# Processor.net
KiCad netlist of a schematic drawn in Altium Designer
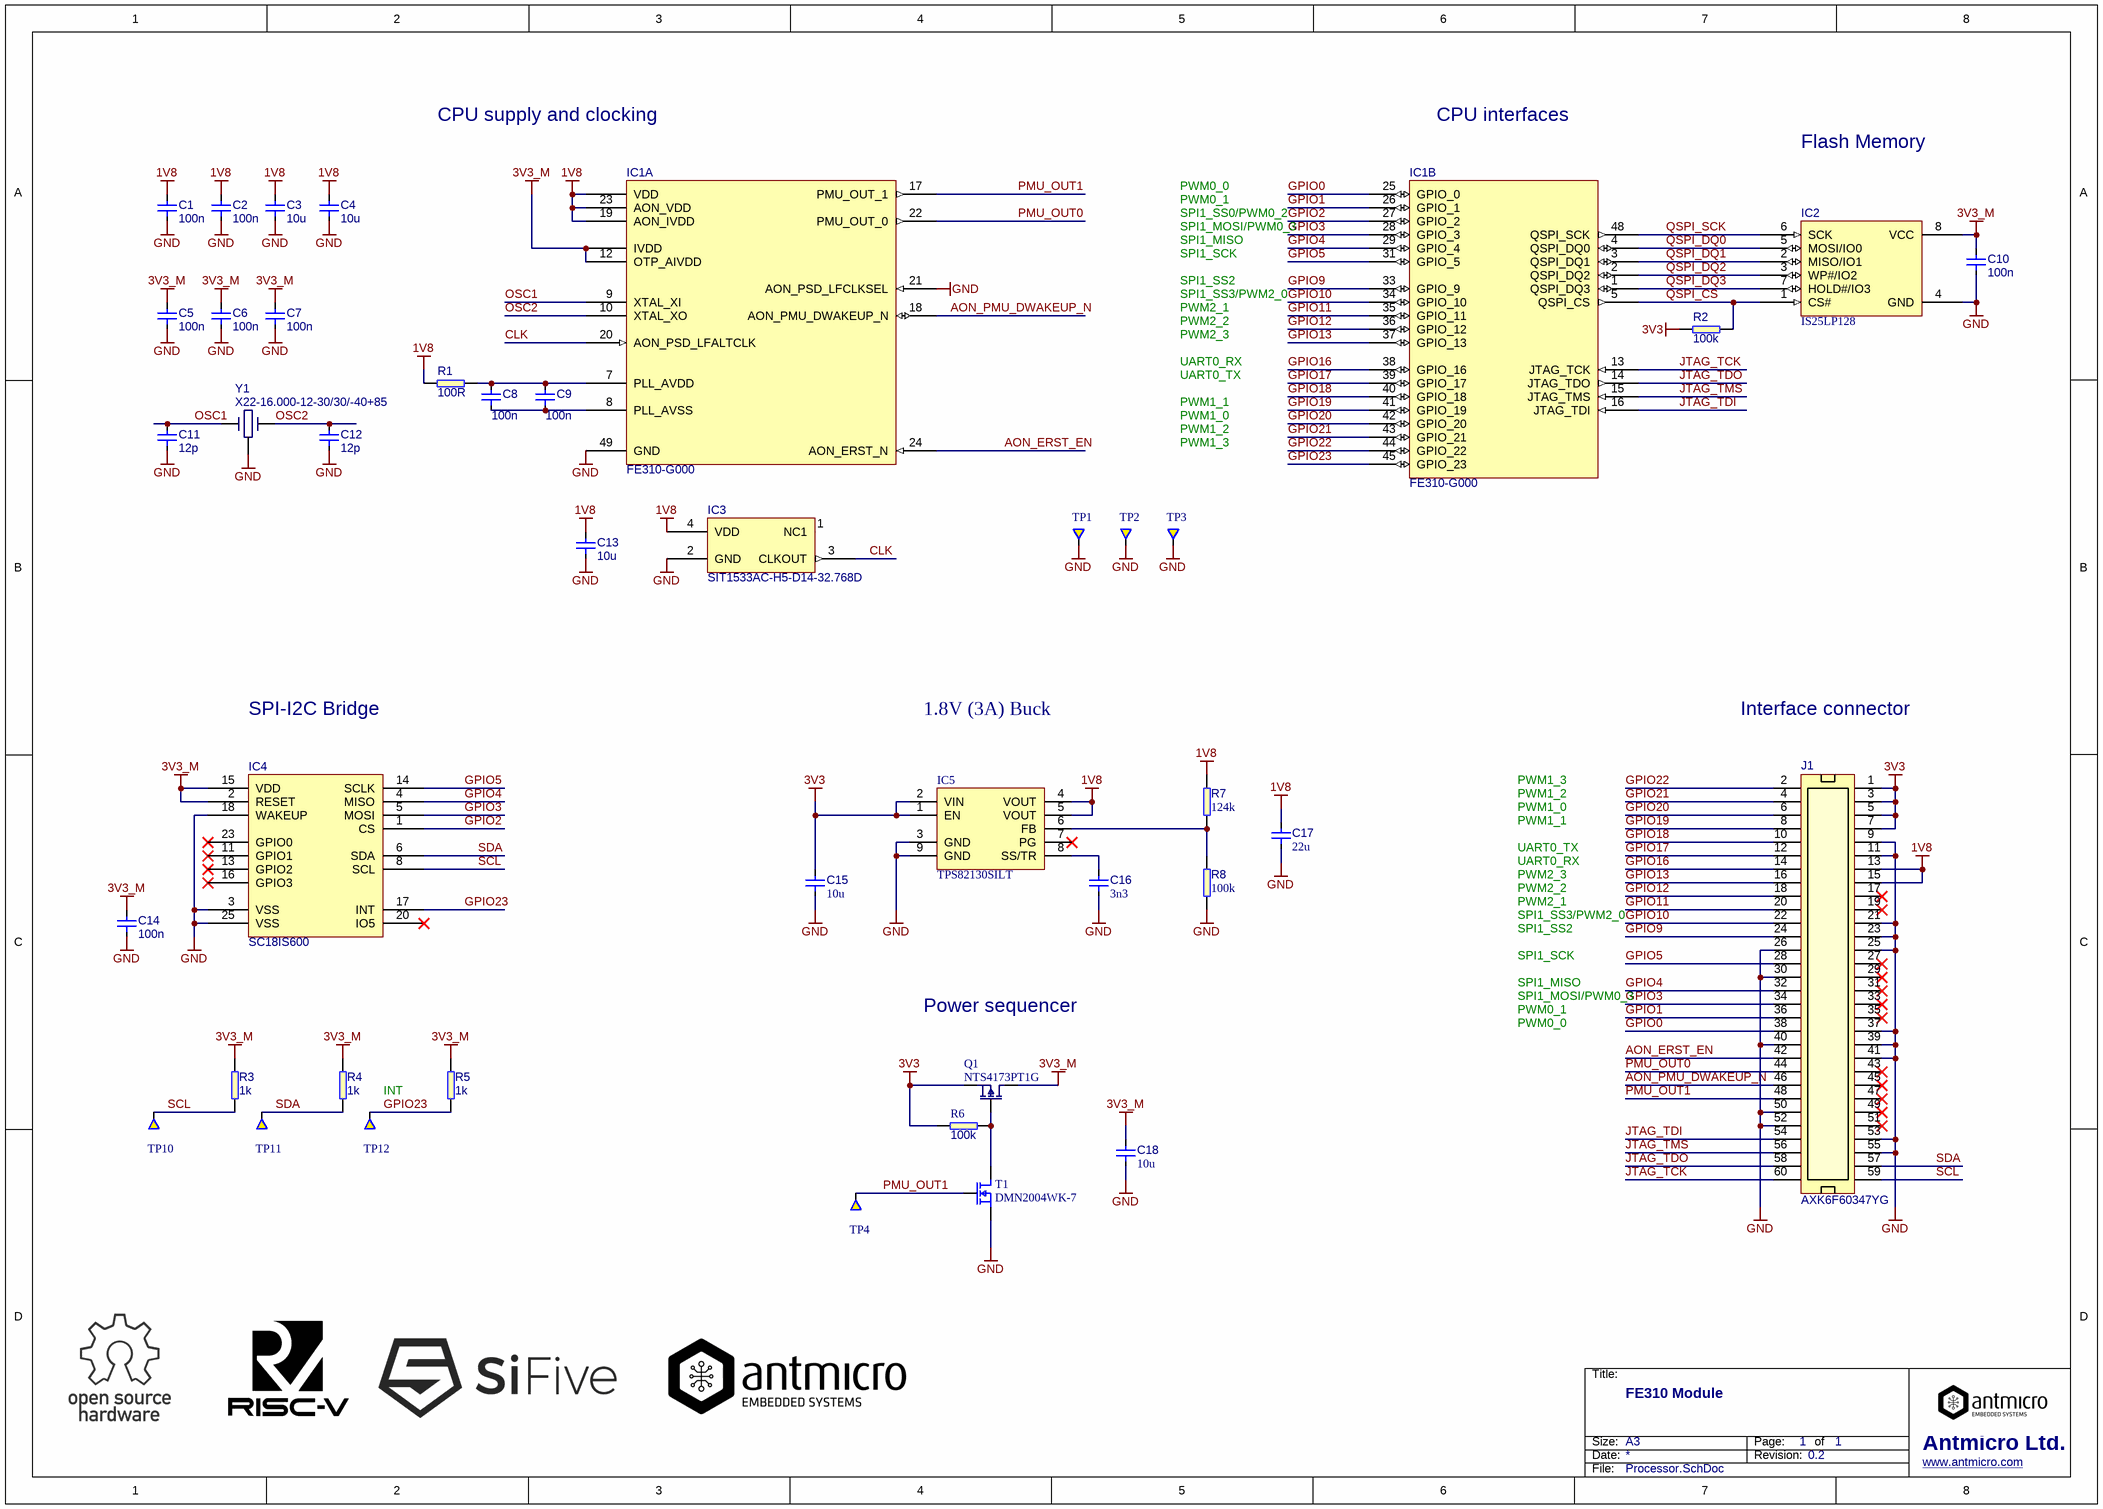
[diagram p0: Processor.SchDoc]

(export (version "E")
  (design (tool "Eeschema 10.0.6"))
  (components
    (comp (ref "C1")
      (value "100n")
      (footprint "0402")
      (description "MLCC SMT Capacitor 100nF 0402")
      (fields (field (name "PART NUMBER") "C_100n_0402") (field (name "MANUFACTURER") "MULTICOMP"))
      (libsource (lib "FE310_Module") (part "C_100n_0402"))
    )
    (comp (ref "C2")
      (value "100n")
      (footprint "0402")
      (description "MLCC SMT Capacitor 100nF 0402")
      (fields (field (name "PART NUMBER") "C_100n_0402") (field (name "MANUFACTURER") "MULTICOMP"))
      (libsource (lib "FE310_Module") (part "C_100n_0402"))
    )
    (comp (ref "C3")
      (value "10u")
      (footprint "0402")
      (description "MLCC SMT Capacitor 10uF 0402")
      (fields (field (name "PART NUMBER") "C_10u_0402") (field (name "MANUFACTURER") "TDK"))
      (libsource (lib "FE310_Module") (part "C_10u_0402"))
    )
    (comp (ref "C4")
      (value "10u")
      (footprint "0402")
      (description "MLCC SMT Capacitor 10uF 0402")
      (fields (field (name "PART NUMBER") "C_10u_0402") (field (name "MANUFACTURER") "TDK"))
      (libsource (lib "FE310_Module") (part "C_10u_0402"))
    )
    (comp (ref "C5")
      (value "100n")
      (footprint "0402")
      (description "MLCC SMT Capacitor 100nF 0402")
      (fields (field (name "PART NUMBER") "C_100n_0402") (field (name "MANUFACTURER") "MULTICOMP"))
      (libsource (lib "FE310_Module") (part "C_100n_0402"))
    )
    (comp (ref "C6")
      (value "100n")
      (footprint "0402")
      (description "MLCC SMT Capacitor 100nF 0402")
      (fields (field (name "PART NUMBER") "C_100n_0402") (field (name "MANUFACTURER") "MULTICOMP"))
      (libsource (lib "FE310_Module") (part "C_100n_0402"))
    )
    (comp (ref "C7")
      (value "100n")
      (footprint "0402")
      (description "MLCC SMT Capacitor 100nF 0402")
      (fields (field (name "PART NUMBER") "C_100n_0402") (field (name "MANUFACTURER") "MULTICOMP"))
      (libsource (lib "FE310_Module") (part "C_100n_0402"))
    )
    (comp (ref "C8")
      (value "100n")
      (footprint "0402")
      (description "MLCC SMT Capacitor 100nF 0402")
      (fields (field (name "PART NUMBER") "C_100n_0402") (field (name "MANUFACTURER") "MULTICOMP"))
      (libsource (lib "FE310_Module") (part "C_100n_0402"))
    )
    (comp (ref "C9")
      (value "100n")
      (footprint "0402")
      (description "MLCC SMT Capacitor 100nF 0402")
      (fields (field (name "PART NUMBER") "C_100n_0402") (field (name "MANUFACTURER") "MULTICOMP"))
      (libsource (lib "FE310_Module") (part "C_100n_0402"))
    )
    (comp (ref "C10")
      (value "100n")
      (footprint "0402")
      (description "MLCC SMT Capacitor 100nF 0402")
      (fields (field (name "PART NUMBER") "C_100n_0402") (field (name "MANUFACTURER") "MULTICOMP"))
      (libsource (lib "FE310_Module") (part "C_100n_0402"))
    )
    (comp (ref "C11")
      (value "12p")
      (footprint "0402")
      (description "MLCC SMT Capacitor 12pF 0402")
      (fields (field (name "PART NUMBER") "C_12p_0402") (field (name "MANUFACTURER") "WALSIN"))
      (libsource (lib "FE310_Module") (part "C_12p_0402"))
    )
    (comp (ref "C12")
      (value "12p")
      (footprint "0402")
      (description "MLCC SMT Capacitor 12pF 0402")
      (fields (field (name "PART NUMBER") "C_12p_0402") (field (name "MANUFACTURER") "WALSIN"))
      (libsource (lib "FE310_Module") (part "C_12p_0402"))
    )
    (comp (ref "C13")
      (value "10u")
      (footprint "0402")
      (description "MLCC SMT Capacitor 10uF 0402")
      (fields (field (name "PART NUMBER") "C_10u_0402") (field (name "MANUFACTURER") "TDK"))
      (libsource (lib "FE310_Module") (part "C_10u_0402"))
    )
    (comp (ref "C14")
      (value "100n")
      (footprint "0402")
      (description "MLCC SMT Capacitor 100nF 0402")
      (fields (field (name "PART NUMBER") "C_100n_0402") (field (name "MANUFACTURER") "MULTICOMP"))
      (libsource (lib "FE310_Module") (part "C_100n_0402"))
    )
    (comp (ref "C15")
      (value "10u")
      (footprint "0402")
      (description "MLCC SMT Capacitor 10uF 0402")
      (fields (field (name "PART NUMBER") "C_10u_0402") (field (name "MANUFACTURER") "TDK"))
      (libsource (lib "FE310_Module") (part "C_10u_0402"))
    )
    (comp (ref "C16")
      (value "3n3")
      (footprint "0402")
      (description "MLCC SMT Capacitor 3.3nF 0402")
      (fields (field (name "PART NUMBER") "C_3n3_0402") (field (name "MANUFACTURER") "MULTICOMP"))
      (libsource (lib "FE310_Module") (part "C_3n3_0402"))
    )
    (comp (ref "C17")
      (value "22u")
      (footprint "0603")
      (description "MLCC SMT Capacitor 22uF 0603")
      (fields (field (name "PART NUMBER") "C_22u_0603") (field (name "MANUFACTURER") "MURATA"))
      (libsource (lib "FE310_Module") (part "C_22_0603"))
    )
    (comp (ref "C18")
      (value "10u")
      (footprint "0402")
      (description "MLCC SMT Capacitor 10uF 0402")
      (fields (field (name "PART NUMBER") "C_10u_0402") (field (name "MANUFACTURER") "TDK"))
      (libsource (lib "FE310_Module") (part "C_10u_0402"))
    )
    (comp (ref "IC1")
      (value "FE310-G000")
      (footprint "FE310-G000")
      (fields (field (name "MANUFACTURER") "FREEDOM"))
      (libsource (lib "FE310_Module") (part "FE310-G000"))
    )
    (comp (ref "IC2")
      (value "IS25LP128")
      (footprint "WSON_6x5mm_8pin")
      (description "Flash Memory 128Mb QPI/QSPI, WSON, RoHS, ET")
      (fields (field (name "PART NUMBER") "IS25LP128-JKLE") (field (name "MANUFACTURER") "ISSI"))
      (libsource (lib "FE310_Module") (part "IS25LP128"))
    )
    (comp (ref "IC3")
      (value "SIT1533AC-H5-D14-32.768D")
      (footprint "SIT1533AC")
      (description "32.768kHz LVCMOS MEMS (Silicon) Oscillator Surface Mount 1.2 V ~ 3.63 V 1.3µA")
      (fields (field (name "MANUFACTURER") "SiTIME"))
      (libsource (lib "FE310_Module") (part "SIT1533AC"))
    )
    (comp (ref "IC4")
      (value "SC18IS600")
      (footprint "QFN-24_4X4MM")
      (description "IC SPI TO I2C BUS 24-HVQFN")
      (fields (field (name "PART NUMBER") "SC18IS600IBS,151") (field (name "MANUFACTURER") "NXP"))
      (libsource (lib "FE310_Module") (part "SC18IS600"))
    )
    (comp (ref "IC5")
      (value "TPS82130SILT")
      (footprint "MicroSIP")
      (description "3-A 17V STEP-DOWN CONVERTER")
      (fields (field (name "MANUFACTURER") "Texas Instruments"))
      (libsource (lib "FE310_Module") (part "TPS82130"))
    )
    (comp (ref "J1")
      (value "AXK6F60347YG")
      (footprint "AXK6F60347YG")
      (description "CONN HEADER BRD/BRD .5MM 60POS")
      (fields (field (name "MANUFACTURER") "PANASONIC"))
      (libsource (lib "FE310_Module") (part "AXK6F60347YG"))
    )
    (comp (ref "Q1")
      (value "NTS4173PT1G")
      (footprint "SC70-3")
      (description "MOSFET P-CH 30V 1.2A SC70-3")
      (fields (field (name "MANUFACTURER") "ON Semiconductor"))
      (libsource (lib "FE310_Module") (part "PMOS"))
    )
    (comp (ref "R1")
      (value "100R")
      (footprint "0402")
      (description "SMT Resistor 100R 0402")
      (fields (field (name "PART NUMBER") "R_100R_0402") (field (name "MANUFACTURER") "BOURNS"))
      (libsource (lib "FE310_Module") (part "R_100R_0402"))
    )
    (comp (ref "R2")
      (value "100k")
      (footprint "0402")
      (description "SMT Resistor 100k 0402")
      (fields (field (name "PART NUMBER") "R_100k_0402") (field (name "MANUFACTURER") "VISHAY"))
      (libsource (lib "FE310_Module") (part "R_100k_0402"))
    )
    (comp (ref "R3")
      (value "1k")
      (footprint "0402")
      (description "SMT Resistor 0402")
      (fields (field (name "PART NUMBER") "R_1k_0402") (field (name "MANUFACTURER") "MULTICOMP"))
      (libsource (lib "FE310_Module") (part "R_1k_0402"))
    )
    (comp (ref "R4")
      (value "1k")
      (footprint "0402")
      (description "SMT Resistor 0402")
      (fields (field (name "PART NUMBER") "R_1k_0402") (field (name "MANUFACTURER") "MULTICOMP"))
      (libsource (lib "FE310_Module") (part "R_1k_0402"))
    )
    (comp (ref "R5")
      (value "1k")
      (footprint "0402")
      (description "SMT Resistor 0402")
      (fields (field (name "PART NUMBER") "R_1k_0402") (field (name "MANUFACTURER") "MULTICOMP"))
      (libsource (lib "FE310_Module") (part "R_1k_0402"))
    )
    (comp (ref "R6")
      (value "100k")
      (footprint "0402")
      (description "SMT Resistor 100k 0402")
      (fields (field (name "PART NUMBER") "R_100k_0402") (field (name "TOLERANCE") "1%"))
      (libsource (lib "AntmicroComponents") (part "R"))
    )
    (comp (ref "R7")
      (value "124k")
      (footprint "0402")
      (description "SMT Resistor 124k 0402")
      (fields (field (name "PART NUMBER") "R_124k_0402") (field (name "MANUFACTURER") "WALSIN"))
      (libsource (lib "FE310_Module") (part "R_124k_0402"))
    )
    (comp (ref "R8")
      (value "100k")
      (footprint "0402")
      (description "SMT Resistor 100k 0402")
      (fields (field (name "PART NUMBER") "R_100k_0402") (field (name "MANUFACTURER") "VISHAY"))
      (libsource (lib "") (part "R_100k_0402_1"))
    )
    (comp (ref "T1")
      (value "DMN2004WK-7")
      (footprint "SC70-3")
      (description "MOSFET N-CH 20V 540MA SC70-3")
      (fields (field (name "MANUFACTURER") "DIODES INC."))
      (libsource (lib "FE310_Module") (part "NMOS"))
    )
    (comp (ref "TP1")
      (value "Testpad")
      (footprint "TP-R-0.7")
      (description "Testpad 1.5mm diameter")
      (libsource (lib "FE310_Module") (part "Testpad"))
    )
    (comp (ref "TP2")
      (value "Testpad")
      (footprint "TP-R-0.7")
      (description "Testpad 1.5mm diameter")
      (libsource (lib "FE310_Module") (part "Testpad"))
    )
    (comp (ref "TP3")
      (value "Testpad")
      (footprint "TP-R-0.7")
      (description "Testpad 1.5mm diameter")
      (libsource (lib "FE310_Module") (part "Testpad"))
    )
    (comp (ref "TP4")
      (value "Testpad")
      (footprint "TP-R-0.7")
      (description "Testpad 1.5mm diameter")
      (libsource (lib "FE310_Module") (part "Testpad"))
    )
    (comp (ref "TP10")
      (value "Testpad")
      (footprint "TP-R-0.7")
      (description "Testpad 1.5mm diameter")
      (libsource (lib "FE310_Module") (part "Testpad"))
    )
    (comp (ref "TP11")
      (value "Testpad")
      (footprint "TP-R-0.7")
      (description "Testpad 1.5mm diameter")
      (libsource (lib "FE310_Module") (part "Testpad"))
    )
    (comp (ref "TP12")
      (value "Testpad")
      (footprint "TP-R-0.7")
      (description "Testpad 1.5mm diameter")
      (libsource (lib "FE310_Module") (part "Testpad"))
    )
    (comp (ref "Y1")
      (value "X22-16.000-12-30/30/-40+85")
      (footprint "CRYSTAL_X22_2.5x2mm")
      (fields
        (field (name "PART NUMBER") "CRYSTAL_16MHz_SMD_2.5x2mm")
        (field (name "MANUFACTURER") "MERCURY UNITED ELECTRONICS")
      )
      (libsource (lib "FE310_Module") (part "CRYSTAL_4PIN"))
    )
  )
  (nets
    (net (code "1") (name "/AON_ERST_EN") (class "Default")
      (node (ref "IC1") (pin "24") (pinfunction "AON_ERST_N_24") (pintype "input"))
      (node (ref "J1") (pin "42") (pinfunction "42_42") (pintype "passive"))
    )
    (net (code "2") (name "/AON_PMU_DWAKEUP_N") (class "Default")
      (node (ref "IC1") (pin "18") (pinfunction "AON_PMU_DWAKEUP_N_18") (pintype "bidirectional"))
      (node (ref "J1") (pin "46") (pinfunction "46_46") (pintype "passive"))
    )
    (net (code "3") (name "/CLK") (class "Default")
      (node (ref "IC1") (pin "20") (pinfunction "AON_PSD_LFALTCLK_20") (pintype "input"))
      (node (ref "IC3") (pin "3") (pinfunction "CLKOUT_3") (pintype "output"))
    )
    (net (code "4") (name "/GPIO0") (class "Default")
      (node (ref "IC1") (pin "25") (pinfunction "GPIO_0_25") (pintype "bidirectional"))
      (node (ref "J1") (pin "38") (pinfunction "38_38") (pintype "passive"))
    )
    (net (code "5") (name "/GPIO1") (class "Default")
      (node (ref "IC1") (pin "26") (pinfunction "GPIO_1_26") (pintype "bidirectional"))
      (node (ref "J1") (pin "36") (pinfunction "36_36") (pintype "passive"))
    )
    (net (code "6") (name "/GPIO2") (class "Default")
      (node (ref "IC1") (pin "27") (pinfunction "GPIO_2_27") (pintype "bidirectional"))
      (node (ref "IC4") (pin "1") (pinfunction "CS_1") (pintype "passive"))
    )
    (net (code "7") (name "/GPIO3") (class "Default")
      (node (ref "IC1") (pin "28") (pinfunction "GPIO_3_28") (pintype "bidirectional"))
      (node (ref "IC4") (pin "5") (pinfunction "MOSI_5") (pintype "passive"))
      (node (ref "J1") (pin "34") (pinfunction "34_34") (pintype "passive"))
    )
    (net (code "8") (name "/GPIO4") (class "Default")
      (node (ref "IC1") (pin "29") (pinfunction "GPIO_4_29") (pintype "bidirectional"))
      (node (ref "IC4") (pin "4") (pinfunction "MISO_4") (pintype "passive"))
      (node (ref "J1") (pin "32") (pinfunction "32_32") (pintype "passive"))
    )
    (net (code "9") (name "/GPIO5") (class "Default")
      (node (ref "IC1") (pin "31") (pinfunction "GPIO_5_31") (pintype "bidirectional"))
      (node (ref "IC4") (pin "14") (pinfunction "SCLK_14") (pintype "passive"))
      (node (ref "J1") (pin "28") (pinfunction "28_28") (pintype "passive"))
    )
    (net (code "10") (name "/GPIO9") (class "Default")
      (node (ref "IC1") (pin "33") (pinfunction "GPIO_9_33") (pintype "bidirectional"))
      (node (ref "J1") (pin "24") (pinfunction "24_24") (pintype "passive"))
    )
    (net (code "11") (name "/GPIO10") (class "Default")
      (node (ref "IC1") (pin "34") (pinfunction "GPIO_10_34") (pintype "bidirectional"))
      (node (ref "J1") (pin "22") (pinfunction "22_22") (pintype "passive"))
    )
    (net (code "12") (name "/GPIO11") (class "Default")
      (node (ref "IC1") (pin "35") (pinfunction "GPIO_11_35") (pintype "bidirectional"))
      (node (ref "J1") (pin "20") (pinfunction "20_20") (pintype "passive"))
    )
    (net (code "13") (name "/GPIO12") (class "Default")
      (node (ref "IC1") (pin "36") (pinfunction "GPIO_12_36") (pintype "bidirectional"))
      (node (ref "J1") (pin "18") (pinfunction "18_18") (pintype "passive"))
    )
    (net (code "14") (name "/GPIO13") (class "Default")
      (node (ref "IC1") (pin "37") (pinfunction "GPIO_13_37") (pintype "bidirectional"))
      (node (ref "J1") (pin "16") (pinfunction "16_16") (pintype "passive"))
    )
    (net (code "15") (name "/GPIO16") (class "Default")
      (node (ref "IC1") (pin "38") (pinfunction "GPIO_16_38") (pintype "bidirectional"))
      (node (ref "J1") (pin "14") (pinfunction "14_14") (pintype "passive"))
    )
    (net (code "16") (name "/GPIO17") (class "Default")
      (node (ref "IC1") (pin "39") (pinfunction "GPIO_17_39") (pintype "bidirectional"))
      (node (ref "J1") (pin "12") (pinfunction "12_12") (pintype "passive"))
    )
    (net (code "17") (name "/GPIO18") (class "Default")
      (node (ref "IC1") (pin "40") (pinfunction "GPIO_18_40") (pintype "bidirectional"))
      (node (ref "J1") (pin "10") (pinfunction "10_10") (pintype "passive"))
    )
    (net (code "18") (name "/GPIO19") (class "Default")
      (node (ref "IC1") (pin "41") (pinfunction "GPIO_19_41") (pintype "bidirectional"))
      (node (ref "J1") (pin "8") (pinfunction "8_8") (pintype "passive"))
    )
    (net (code "19") (name "/GPIO20") (class "Default")
      (node (ref "IC1") (pin "42") (pinfunction "GPIO_20_42") (pintype "bidirectional"))
      (node (ref "J1") (pin "6") (pinfunction "6_6") (pintype "passive"))
    )
    (net (code "20") (name "/GPIO21") (class "Default")
      (node (ref "IC1") (pin "43") (pinfunction "GPIO_21_43") (pintype "bidirectional"))
      (node (ref "J1") (pin "4") (pinfunction "4_4") (pintype "passive"))
    )
    (net (code "21") (name "/GPIO22") (class "Default")
      (node (ref "IC1") (pin "44") (pinfunction "GPIO_22_44") (pintype "bidirectional"))
      (node (ref "J1") (pin "2") (pinfunction "2_2") (pintype "passive"))
    )
    (net (code "22") (name "/GPIO23") (class "Default")
      (node (ref "IC1") (pin "45") (pinfunction "GPIO_23_45") (pintype "bidirectional"))
      (node (ref "IC4") (pin "17") (pinfunction "INT_17") (pintype "passive"))
      (node (ref "R5") (pin "2") (pintype "passive"))
      (node (ref "TP12") (pin "1") (pintype "passive"))
    )
    (net (code "23") (name "/JTAG_TCK") (class "Default")
      (node (ref "IC1") (pin "13") (pinfunction "JTAG_TCK_13") (pintype "input"))
      (node (ref "J1") (pin "60") (pinfunction "60_60") (pintype "passive"))
    )
    (net (code "24") (name "/JTAG_TDI") (class "Default")
      (node (ref "IC1") (pin "16") (pinfunction "JTAG_TDI_16") (pintype "input"))
      (node (ref "J1") (pin "54") (pinfunction "54_54") (pintype "passive"))
    )
    (net (code "25") (name "/JTAG_TDO") (class "Default")
      (node (ref "IC1") (pin "14") (pinfunction "JTAG_TDO_14") (pintype "output"))
      (node (ref "J1") (pin "58") (pinfunction "58_58") (pintype "passive"))
    )
    (net (code "26") (name "/JTAG_TMS") (class "Default")
      (node (ref "IC1") (pin "15") (pinfunction "JTAG_TMS_15") (pintype "input"))
      (node (ref "J1") (pin "56") (pinfunction "56_56") (pintype "passive"))
    )
    (net (code "27") (name "/OSC1") (class "Default")
      (node (ref "C11") (pin "2") (pinfunction "2_2") (pintype "passive"))
      (node (ref "IC1") (pin "9") (pinfunction "XTAL_XI_9") (pintype "passive"))
      (node (ref "Y1") (pin "1") (pinfunction "1_1") (pintype "passive"))
    )
    (net (code "28") (name "/OSC2") (class "Default")
      (node (ref "C12") (pin "2") (pinfunction "2_2") (pintype "passive"))
      (node (ref "IC1") (pin "10") (pinfunction "XTAL_XO_10") (pintype "passive"))
      (node (ref "Y1") (pin "3") (pinfunction "3_3") (pintype "passive"))
    )
    (net (code "29") (name "/PMU_OUT0") (class "Default")
      (node (ref "IC1") (pin "22") (pinfunction "PMU_OUT_0_22") (pintype "output"))
      (node (ref "J1") (pin "44") (pinfunction "44_44") (pintype "passive"))
    )
    (net (code "30") (name "/PMU_OUT1") (class "Default")
      (node (ref "IC1") (pin "17") (pinfunction "PMU_OUT_1_17") (pintype "output"))
      (node (ref "J1") (pin "48") (pinfunction "48_48") (pintype "passive"))
      (node (ref "T1") (pin "1") (pinfunction "G_1") (pintype "passive"))
      (node (ref "TP4") (pin "1") (pintype "passive"))
    )
    (net (code "31") (name "/QSPI_CS") (class "Default")
      (node (ref "IC1") (pin "5") (pinfunction "QSPI_CS_5") (pintype "output"))
      (node (ref "IC2") (pin "1") (pinfunction "CS#_1") (pintype "input"))
      (node (ref "R2") (pin "2") (pintype "passive"))
    )
    (net (code "32") (name "/QSPI_DQ0") (class "Default")
      (node (ref "IC1") (pin "4") (pinfunction "QSPI_DQ0_4") (pintype "bidirectional"))
      (node (ref "IC2") (pin "5") (pinfunction "MOSI/IO0_5") (pintype "bidirectional"))
    )
    (net (code "33") (name "/QSPI_DQ1") (class "Default")
      (node (ref "IC1") (pin "3") (pinfunction "QSPI_DQ1_3") (pintype "bidirectional"))
      (node (ref "IC2") (pin "2") (pinfunction "MISO/IO1_2") (pintype "bidirectional"))
    )
    (net (code "34") (name "/QSPI_DQ2") (class "Default")
      (node (ref "IC1") (pin "2") (pinfunction "QSPI_DQ2_2") (pintype "bidirectional"))
      (node (ref "IC2") (pin "3") (pinfunction "WP#/IO2_3") (pintype "bidirectional"))
    )
    (net (code "35") (name "/QSPI_DQ3") (class "Default")
      (node (ref "IC1") (pin "1") (pinfunction "QSPI_DQ3_1") (pintype "bidirectional"))
      (node (ref "IC2") (pin "7") (pinfunction "HOLD#/IO3_7") (pintype "bidirectional"))
    )
    (net (code "36") (name "/QSPI_SCK") (class "Default")
      (node (ref "IC1") (pin "48") (pinfunction "QSPI_SCK_48") (pintype "output"))
      (node (ref "IC2") (pin "6") (pinfunction "SCK_6") (pintype "input"))
    )
    (net (code "37") (name "/SCL") (class "Default")
      (node (ref "IC4") (pin "8") (pinfunction "SCL_8") (pintype "passive"))
      (node (ref "J1") (pin "59") (pinfunction "59_59") (pintype "passive"))
      (node (ref "R3") (pin "2") (pintype "passive"))
      (node (ref "TP10") (pin "1") (pintype "passive"))
    )
    (net (code "38") (name "/SDA") (class "Default")
      (node (ref "IC4") (pin "6") (pinfunction "SDA_6") (pintype "passive"))
      (node (ref "J1") (pin "57") (pinfunction "57_57") (pintype "passive"))
      (node (ref "R4") (pin "2") (pintype "passive"))
      (node (ref "TP11") (pin "1") (pintype "passive"))
    )
    (net (code "39") (name "1V8") (class "Default")
      (node (ref "C1") (pin "2") (pinfunction "2_2") (pintype "passive"))
      (node (ref "C13") (pin "2") (pinfunction "2_2") (pintype "passive"))
      (node (ref "C17") (pin "2") (pinfunction "2_2") (pintype "passive"))
      (node (ref "C2") (pin "2") (pinfunction "2_2") (pintype "passive"))
      (node (ref "C3") (pin "2") (pinfunction "2_2") (pintype "passive"))
      (node (ref "C4") (pin "2") (pinfunction "2_2") (pintype "passive"))
      (node (ref "IC1") (pin "19") (pinfunction "AON_IVDD_19") (pintype "power_in"))
      (node (ref "IC1") (pin "23") (pinfunction "AON_VDD_23") (pintype "power_in"))
      (node (ref "IC1") (pin "VDD") (pinfunction "VDD_VDD") (pintype "power_in"))
      (node (ref "IC3") (pin "4") (pinfunction "VDD_4") (pintype "power_in"))
      (node (ref "IC5") (pin "4") (pinfunction "VOUT_4") (pintype "passive"))
      (node (ref "IC5") (pin "5") (pinfunction "VOUT_5") (pintype "passive"))
      (node (ref "J1") (pin "13") (pinfunction "13_13") (pintype "passive"))
      (node (ref "J1") (pin "15") (pinfunction "15_15") (pintype "passive"))
      (node (ref "R1") (pin "1") (pintype "passive"))
      (node (ref "R7") (pin "1") (pintype "passive"))
    )
    (net (code "40") (name "3V3") (class "Default")
      (node (ref "C15") (pin "2") (pinfunction "2_2") (pintype "passive"))
      (node (ref "IC5") (pin "1") (pinfunction "EN_1") (pintype "passive"))
      (node (ref "IC5") (pin "2") (pinfunction "VIN_2") (pintype "passive"))
      (node (ref "J1") (pin "1") (pinfunction "1_1") (pintype "passive"))
      (node (ref "J1") (pin "3") (pinfunction "3_3") (pintype "passive"))
      (node (ref "J1") (pin "5") (pinfunction "5_5") (pintype "passive"))
      (node (ref "J1") (pin "7") (pinfunction "7_7") (pintype "passive"))
      (node (ref "Q1") (pin "2") (pinfunction "S_2") (pintype "passive"))
      (node (ref "R2") (pin "1") (pintype "passive"))
      (node (ref "R6") (pin "1") (pintype "passive"))
    )
    (net (code "41") (name "3V3_M") (class "Default")
      (node (ref "C10") (pin "2") (pinfunction "2_2") (pintype "passive"))
      (node (ref "C14") (pin "2") (pinfunction "2_2") (pintype "passive"))
      (node (ref "C18") (pin "2") (pinfunction "2_2") (pintype "passive"))
      (node (ref "C5") (pin "2") (pinfunction "2_2") (pintype "passive"))
      (node (ref "C6") (pin "2") (pinfunction "2_2") (pintype "passive"))
      (node (ref "C7") (pin "2") (pinfunction "2_2") (pintype "passive"))
      (node (ref "IC1") (pin "12") (pinfunction "OTP_AIVDD_12") (pintype "power_in"))
      (node (ref "IC1") (pin "IVDD") (pinfunction "IVDD_IVDD") (pintype "power_in"))
      (node (ref "IC2") (pin "8") (pinfunction "VCC_8") (pintype "power_in"))
      (node (ref "IC4") (pin "15") (pinfunction "VDD_15") (pintype "passive"))
      (node (ref "IC4") (pin "2") (pinfunction "RESET_2") (pintype "passive"))
      (node (ref "Q1") (pin "3") (pinfunction "D_3") (pintype "passive"))
      (node (ref "R3") (pin "1") (pintype "passive"))
      (node (ref "R4") (pin "1") (pintype "passive"))
      (node (ref "R5") (pin "1") (pintype "passive"))
    )
    (net (code "42") (name "GND") (class "Default")
      (node (ref "C1") (pin "1") (pinfunction "1_1") (pintype "passive"))
      (node (ref "C10") (pin "1") (pinfunction "1_1") (pintype "passive"))
      (node (ref "C11") (pin "1") (pinfunction "1_1") (pintype "passive"))
      (node (ref "C12") (pin "1") (pinfunction "1_1") (pintype "passive"))
      (node (ref "C13") (pin "1") (pinfunction "1_1") (pintype "passive"))
      (node (ref "C14") (pin "1") (pinfunction "1_1") (pintype "passive"))
      (node (ref "C15") (pin "1") (pinfunction "1_1") (pintype "passive"))
      (node (ref "C16") (pin "1") (pinfunction "1_1") (pintype "passive"))
      (node (ref "C17") (pin "1") (pinfunction "1_1") (pintype "passive"))
      (node (ref "C18") (pin "1") (pinfunction "1_1") (pintype "passive"))
      (node (ref "C2") (pin "1") (pinfunction "1_1") (pintype "passive"))
      (node (ref "C3") (pin "1") (pinfunction "1_1") (pintype "passive"))
      (node (ref "C4") (pin "1") (pinfunction "1_1") (pintype "passive"))
      (node (ref "C5") (pin "1") (pinfunction "1_1") (pintype "passive"))
      (node (ref "C6") (pin "1") (pinfunction "1_1") (pintype "passive"))
      (node (ref "C7") (pin "1") (pinfunction "1_1") (pintype "passive"))
      (node (ref "IC1") (pin "21") (pinfunction "AON_PSD_LFCLKSEL_21") (pintype "input"))
      (node (ref "IC1") (pin "49") (pinfunction "GND_49") (pintype "passive"))
      (node (ref "IC2") (pin "4") (pinfunction "GND_4") (pintype "passive"))
      (node (ref "IC3") (pin "2") (pinfunction "GND_2") (pintype "passive"))
      (node (ref "IC4") (pin "18") (pinfunction "WAKEUP_18") (pintype "passive"))
      (node (ref "IC4") (pin "25") (pinfunction "VSS_25") (pintype "passive"))
      (node (ref "IC4") (pin "3") (pinfunction "VSS_3") (pintype "passive"))
      (node (ref "IC5") (pin "3") (pinfunction "GND_3") (pintype "passive"))
      (node (ref "IC5") (pin "9") (pinfunction "GND_9") (pintype "passive"))
      (node (ref "J1") (pin "11") (pinfunction "11_11") (pintype "passive"))
      (node (ref "J1") (pin "21") (pinfunction "21_21") (pintype "passive"))
      (node (ref "J1") (pin "23") (pinfunction "23_23") (pintype "passive"))
      (node (ref "J1") (pin "25") (pinfunction "25_25") (pintype "passive"))
      (node (ref "J1") (pin "26") (pinfunction "26_26") (pintype "passive"))
      (node (ref "J1") (pin "30") (pinfunction "30_30") (pintype "passive"))
      (node (ref "J1") (pin "37") (pinfunction "37_37") (pintype "passive"))
      (node (ref "J1") (pin "39") (pinfunction "39_39") (pintype "passive"))
      (node (ref "J1") (pin "40") (pinfunction "40_40") (pintype "passive"))
      (node (ref "J1") (pin "41") (pinfunction "41_41") (pintype "passive"))
      (node (ref "J1") (pin "50") (pinfunction "50_50") (pintype "passive"))
      (node (ref "J1") (pin "52") (pinfunction "52_52") (pintype "passive"))
      (node (ref "J1") (pin "53") (pinfunction "53_53") (pintype "passive"))
      (node (ref "J1") (pin "55") (pinfunction "55_55") (pintype "passive"))
      (node (ref "J1") (pin "9") (pinfunction "9_9") (pintype "passive"))
      (node (ref "R8") (pin "2") (pintype "passive"))
      (node (ref "T1") (pin "2") (pinfunction "S_2") (pintype "passive"))
      (node (ref "TP1") (pin "1") (pintype "passive"))
      (node (ref "TP2") (pin "1") (pintype "passive"))
      (node (ref "TP3") (pin "1") (pintype "passive"))
      (node (ref "Y1") (pin "GND") (pinfunction "GND_GND") (pintype "passive"))
    )
    (net (code "43") (name "Net-(IC1A-PLL_AVDD)") (class "Default")
      (node (ref "C8") (pin "2") (pinfunction "2_2") (pintype "passive"))
      (node (ref "C9") (pin "2") (pinfunction "2_2") (pintype "passive"))
      (node (ref "IC1") (pin "7") (pinfunction "PLL_AVDD_7") (pintype "power_in"))
      (node (ref "R1") (pin "2") (pintype "passive"))
    )
    (net (code "44") (name "Net-(IC1A-PLL_AVSS)") (class "Default")
      (node (ref "C8") (pin "1") (pinfunction "1_1") (pintype "passive"))
      (node (ref "C9") (pin "1") (pinfunction "1_1") (pintype "passive"))
      (node (ref "IC1") (pin "8") (pinfunction "PLL_AVSS_8") (pintype "passive"))
    )
    (net (code "45") (name "Net-(IC5-FB)") (class "Default")
      (node (ref "IC5") (pin "6") (pinfunction "FB_6") (pintype "passive"))
      (node (ref "R7") (pin "2") (pintype "passive"))
      (node (ref "R8") (pin "1") (pintype "passive"))
    )
    (net (code "46") (name "Net-(IC5-SS{slash}TR)") (class "Default")
      (node (ref "C16") (pin "2") (pinfunction "2_2") (pintype "passive"))
      (node (ref "IC5") (pin "8") (pinfunction "SS/TR_8") (pintype "passive"))
    )
    (net (code "47") (name "Net-(Q1-G)") (class "Default")
      (node (ref "Q1") (pin "1") (pinfunction "G_1") (pintype "passive"))
      (node (ref "R6") (pin "2") (pintype "passive"))
      (node (ref "T1") (pin "3") (pinfunction "D_3") (pintype "passive"))
    )
    (net (code "48") (name "unconnected-(IC3-NC1-Pad1)") (class "Default")
      (node (ref "IC3") (pin "1") (pinfunction "NC1_1") (pintype "passive"))
    )
    (net (code "49") (name "unconnected-(IC4-GPIO0-Pad23)") (class "Default")
      (node (ref "IC4") (pin "23") (pinfunction "GPIO0_23") (pintype "passive+no_connect"))
    )
    (net (code "50") (name "unconnected-(IC4-GPIO1-Pad11)") (class "Default")
      (node (ref "IC4") (pin "11") (pinfunction "GPIO1_11") (pintype "passive+no_connect"))
    )
    (net (code "51") (name "unconnected-(IC4-GPIO2-Pad13)") (class "Default")
      (node (ref "IC4") (pin "13") (pinfunction "GPIO2_13") (pintype "passive+no_connect"))
    )
    (net (code "52") (name "unconnected-(IC4-GPIO3-Pad16)") (class "Default")
      (node (ref "IC4") (pin "16") (pinfunction "GPIO3_16") (pintype "passive+no_connect"))
    )
    (net (code "53") (name "unconnected-(IC4-IO5-Pad20)") (class "Default")
      (node (ref "IC4") (pin "20") (pinfunction "IO5_20") (pintype "passive+no_connect"))
    )
    (net (code "54") (name "unconnected-(IC5-PG-Pad7)") (class "Default")
      (node (ref "IC5") (pin "7") (pinfunction "PG_7") (pintype "passive+no_connect"))
    )
    (net (code "55") (name "unconnected-(J1-Pad17)") (class "Default")
      (node (ref "J1") (pin "17") (pinfunction "17_17") (pintype "passive+no_connect"))
    )
    (net (code "56") (name "unconnected-(J1-Pad19)") (class "Default")
      (node (ref "J1") (pin "19") (pinfunction "19_19") (pintype "passive+no_connect"))
    )
    (net (code "57") (name "unconnected-(J1-Pad27)") (class "Default")
      (node (ref "J1") (pin "27") (pinfunction "27_27") (pintype "passive+no_connect"))
    )
    (net (code "58") (name "unconnected-(J1-Pad29)") (class "Default")
      (node (ref "J1") (pin "29") (pinfunction "29_29") (pintype "passive+no_connect"))
    )
    (net (code "59") (name "unconnected-(J1-Pad31)") (class "Default")
      (node (ref "J1") (pin "31") (pinfunction "31_31") (pintype "passive+no_connect"))
    )
    (net (code "60") (name "unconnected-(J1-Pad33)") (class "Default")
      (node (ref "J1") (pin "33") (pinfunction "33_33") (pintype "passive+no_connect"))
    )
    (net (code "61") (name "unconnected-(J1-Pad35)") (class "Default")
      (node (ref "J1") (pin "35") (pinfunction "35_35") (pintype "passive+no_connect"))
    )
    (net (code "62") (name "unconnected-(J1-Pad43)") (class "Default")
      (node (ref "J1") (pin "43") (pinfunction "43_43") (pintype "passive+no_connect"))
    )
    (net (code "63") (name "unconnected-(J1-Pad45)") (class "Default")
      (node (ref "J1") (pin "45") (pinfunction "45_45") (pintype "passive+no_connect"))
    )
    (net (code "64") (name "unconnected-(J1-Pad47)") (class "Default")
      (node (ref "J1") (pin "47") (pinfunction "47_47") (pintype "passive+no_connect"))
    )
    (net (code "65") (name "unconnected-(J1-Pad49)") (class "Default")
      (node (ref "J1") (pin "49") (pinfunction "49_49") (pintype "passive+no_connect"))
    )
    (net (code "66") (name "unconnected-(J1-Pad51)") (class "Default")
      (node (ref "J1") (pin "51") (pinfunction "51_51") (pintype "passive+no_connect"))
    )
  )
)
